# Sheet1.net
KiCad netlist of a schematic drawn in Altium Designer
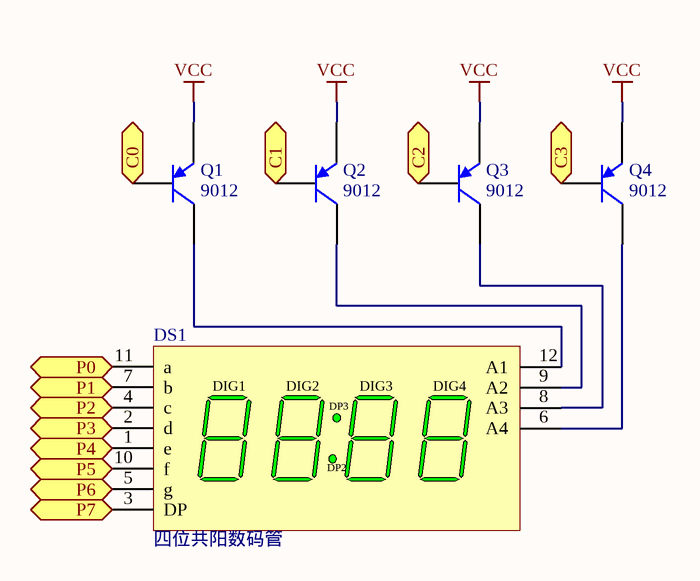
[diagram p0: Sheet1.SchDoc]

(export (version "E")
  (design (tool "Eeschema 10.0.6"))
  (components
    (comp (ref "DS1")
      (value "四位共阳数码管")
      (footprint "B-88")
      (description "14.22 mm Untinted, 88:88 4-Digit 7-Segment Display: CA, Gray Surface")
      (fields (field (name "PUBLISHER") "Altium Limited"))
      (libsource (lib "Agilent LED Display 7-Segment, 4-Digit") (part "HDSP-B08G"))
    )
    (comp (ref "Q1")
      (value "9012")
      (footprint "TO-92A")
      (description "PNP General Purpose Amplifier")
      (fields (field (name "PUBLISHER") "Altium Limited"))
      (libsource (lib "Miscellaneous Devices") (part "2N3906"))
    )
    (comp (ref "Q2")
      (value "9012")
      (footprint "TO-92A")
      (description "PNP General Purpose Amplifier")
      (fields (field (name "PUBLISHER") "Altium Limited"))
      (libsource (lib "Miscellaneous Devices") (part "2N3906"))
    )
    (comp (ref "Q3")
      (value "9012")
      (footprint "TO-92A")
      (description "PNP General Purpose Amplifier")
      (fields (field (name "PUBLISHER") "Altium Limited"))
      (libsource (lib "Miscellaneous Devices") (part "2N3906"))
    )
    (comp (ref "Q4")
      (value "9012")
      (footprint "TO-92A")
      (description "PNP General Purpose Amplifier")
      (fields (field (name "PUBLISHER") "Altium Limited"))
      (libsource (lib "Miscellaneous Devices") (part "2N3906"))
    )
  )
  (nets
    (net (code "1") (name "/C0") (class "Default")
      (node (ref "Q1") (pin "2") (pinfunction "B_2") (pintype "passive"))
    )
    (net (code "2") (name "/C1") (class "Default")
      (node (ref "Q2") (pin "2") (pinfunction "B_2") (pintype "passive"))
    )
    (net (code "3") (name "/C2") (class "Default")
      (node (ref "Q3") (pin "2") (pinfunction "B_2") (pintype "passive"))
    )
    (net (code "4") (name "/C3") (class "Default")
      (node (ref "Q4") (pin "2") (pinfunction "B_2") (pintype "passive"))
    )
    (net (code "5") (name "/P0") (class "Default")
      (node (ref "DS1") (pin "11") (pinfunction "a_11") (pintype "passive"))
    )
    (net (code "6") (name "/P1") (class "Default")
      (node (ref "DS1") (pin "7") (pinfunction "b_7") (pintype "passive"))
    )
    (net (code "7") (name "/P2") (class "Default")
      (node (ref "DS1") (pin "4") (pinfunction "c_4") (pintype "passive"))
    )
    (net (code "8") (name "/P3") (class "Default")
      (node (ref "DS1") (pin "2") (pinfunction "d_2") (pintype "passive"))
    )
    (net (code "9") (name "/P4") (class "Default")
      (node (ref "DS1") (pin "1") (pinfunction "e_1") (pintype "passive"))
    )
    (net (code "10") (name "/P5") (class "Default")
      (node (ref "DS1") (pin "10") (pinfunction "f_10") (pintype "passive"))
    )
    (net (code "11") (name "/P6") (class "Default")
      (node (ref "DS1") (pin "5") (pinfunction "g_5") (pintype "passive"))
    )
    (net (code "12") (name "/P7") (class "Default")
      (node (ref "DS1") (pin "3") (pinfunction "DP_3") (pintype "passive"))
    )
    (net (code "13") (name "Net-(DS1-A1)") (class "Default")
      (node (ref "DS1") (pin "12") (pinfunction "A1_12") (pintype "passive"))
      (node (ref "Q1") (pin "3") (pinfunction "C_3") (pintype "passive"))
    )
    (net (code "14") (name "Net-(DS1-A2)") (class "Default")
      (node (ref "DS1") (pin "9") (pinfunction "A2_9") (pintype "passive"))
      (node (ref "Q2") (pin "3") (pinfunction "C_3") (pintype "passive"))
    )
    (net (code "15") (name "Net-(DS1-A3)") (class "Default")
      (node (ref "DS1") (pin "8") (pinfunction "A3_8") (pintype "passive"))
      (node (ref "Q3") (pin "3") (pinfunction "C_3") (pintype "passive"))
    )
    (net (code "16") (name "Net-(DS1-A4)") (class "Default")
      (node (ref "DS1") (pin "6") (pinfunction "A4_6") (pintype "passive"))
      (node (ref "Q4") (pin "3") (pinfunction "C_3") (pintype "passive"))
    )
    (net (code "17") (name "VCC") (class "Default")
      (node (ref "Q1") (pin "1") (pinfunction "E_1") (pintype "passive"))
      (node (ref "Q2") (pin "1") (pinfunction "E_1") (pintype "passive"))
      (node (ref "Q3") (pin "1") (pinfunction "E_1") (pintype "passive"))
      (node (ref "Q4") (pin "1") (pinfunction "E_1") (pintype "passive"))
    )
  )
)
